# ESP32-XTonUINO_Buttons.net
KiCad netlist of a schematic drawn in EAGLE
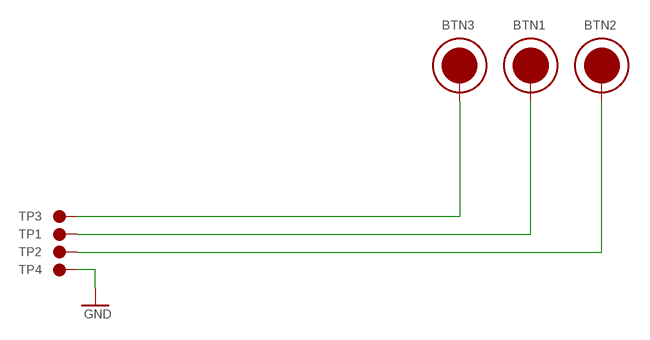
[diagram p0: schematic, sheet 1]

(export (version "E")
  (design (tool "Eeschema 10.0.6"))
  (components
    (comp (ref "BTN1")
      (value "TOUCHBTN")
      (footprint "eagle-import:TOUCHBTN")
      (libsource (lib "eagle-import") (part "TOUCHBTN"))
    )
    (comp (ref "BTN2")
      (value "TOUCHBTN")
      (footprint "eagle-import:TOUCHBTN")
      (libsource (lib "eagle-import") (part "TOUCHBTN"))
    )
    (comp (ref "BTN3")
      (value "TOUCHBTN")
      (footprint "eagle-import:TOUCHBTN")
      (libsource (lib "eagle-import") (part "TOUCHBTN"))
    )
    (comp (ref "TP1")
      (value "TESTPINL")
      (footprint "eagle-import:TESTPAD_L")
      (libsource (lib "eagle-import") (part "TESTPINL"))
    )
    (comp (ref "TP2")
      (value "TESTPINL")
      (footprint "eagle-import:TESTPAD_L")
      (libsource (lib "eagle-import") (part "TESTPINL"))
    )
    (comp (ref "TP3")
      (value "TESTPINL")
      (footprint "eagle-import:TESTPAD_L")
      (libsource (lib "eagle-import") (part "TESTPINL"))
    )
    (comp (ref "TP4")
      (value "TESTPINL")
      (footprint "eagle-import:TESTPAD_L")
      (libsource (lib "eagle-import") (part "TESTPINL"))
    )
  )
  (nets
    (net (code "1") (name "GND") (class "Default")
      (node (ref "TP4") (pin "TP") (pinfunction "TP_TP") (pintype "passive"))
    )
    (net (code "2") (name "Net-(BTN1-1)") (class "Default")
      (node (ref "BTN1") (pin "BTN") (pinfunction "1_BTN") (pintype "passive"))
      (node (ref "TP1") (pin "TP") (pinfunction "TP_TP") (pintype "passive"))
    )
    (net (code "3") (name "Net-(BTN2-1)") (class "Default")
      (node (ref "BTN2") (pin "BTN") (pinfunction "1_BTN") (pintype "passive"))
      (node (ref "TP2") (pin "TP") (pinfunction "TP_TP") (pintype "passive"))
    )
    (net (code "4") (name "Net-(BTN3-1)") (class "Default")
      (node (ref "BTN3") (pin "BTN") (pinfunction "1_BTN") (pintype "passive"))
      (node (ref "TP3") (pin "TP") (pinfunction "TP_TP") (pintype "passive"))
    )
  )
)
